# CAN_Module.net
KiCad netlist of a schematic drawn in Altium Designer
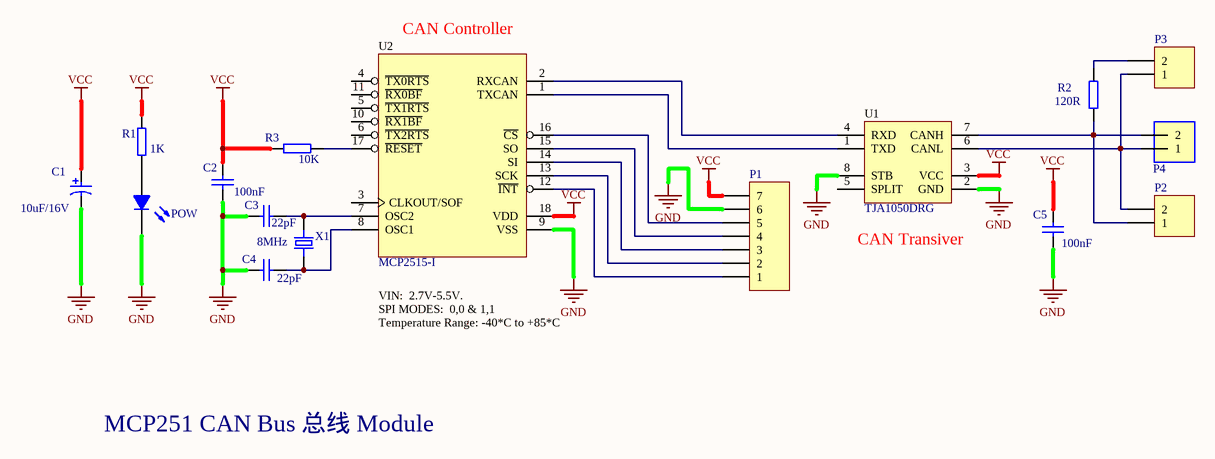
[diagram p0: CAN_Module.SchDoc]

(export (version "E")
  (design (tool "Eeschema 10.0.6"))
  (components
    (comp (ref "C1")
      (value "10uF/16V")
      (footprint "tantalum  A")
      (description "SMD Tantalum Capacitor")
      (libsource (lib "adafruit") (part "Cap_Tantalum"))
    )
    (comp (ref "C2")
      (value "100nF")
      (footprint "C0603")
      (description "Capacitor, X5R, ±10%, 6.3V")
      (fields
        (field (name "PART NUMBER") "C0603-N.C.")
        (field (name "MANUFACTURER") "N.A.")
        (field (name "PUBLISHER") "Nordic Semiconductor")
      )
      (libsource (lib "adafruit") (part "Cap_0603"))
    )
    (comp (ref "C3")
      (value "22pF")
      (footprint "C0603")
      (description "Capacitor, X5R, ±10%, 6.3V")
      (fields
        (field (name "PART NUMBER") "C0603-N.C.")
        (field (name "MANUFACTURER") "N.A.")
        (field (name "PUBLISHER") "Nordic Semiconductor")
      )
      (libsource (lib "adafruit") (part "Cap_0603"))
    )
    (comp (ref "C4")
      (value "22pF")
      (footprint "C0603")
      (description "Capacitor, X5R, ±10%, 6.3V")
      (fields
        (field (name "PART NUMBER") "C0603-N.C.")
        (field (name "MANUFACTURER") "N.A.")
        (field (name "PUBLISHER") "Nordic Semiconductor")
      )
      (libsource (lib "adafruit") (part "Cap_0603"))
    )
    (comp (ref "C5")
      (value "100nF")
      (footprint "C0603")
      (description "Capacitor, X5R, ±10%, 6.3V")
      (fields
        (field (name "PART NUMBER") "C0603-N.C.")
        (field (name "MANUFACTURER") "N.A.")
        (field (name "PUBLISHER") "Nordic Semiconductor")
      )
      (libsource (lib "adafruit") (part "Cap_0603"))
    )
    (comp (ref "P1")
      (value "Header 7")
      (footprint "HDR1X7")
      (description "Header, 7-Pin")
      (fields (field (name "PUBLISHER") "Altium Limited"))
      (libsource (lib "Miscellaneous Connectors") (part "Header 7"))
    )
    (comp (ref "P2")
      (value "Header 2")
      (footprint "HDR1X2")
      (description "Header, 2-Pin")
      (fields (field (name "PUBLISHER") "Altium Limited"))
      (libsource (lib "adafruit") (part "Header 2"))
    )
    (comp (ref "P3")
      (value "Header 2")
      (footprint "HDR1X2")
      (description "Header, 2-Pin")
      (fields (field (name "PUBLISHER") "Altium Limited"))
      (libsource (lib "adafruit") (part "Header 2"))
    )
    (comp (ref "P4")
      (value "Terminal Block 3.5mmPitch: 3,5 mmNumber of pins: 2Created by Rembrandt Electronicswww.rembrandtelectronics.com")
      (footprint "TERMINAL-BLOCK-2-PIN-3.5MM-ROUND-PAD")
      (description "Screw Terminal 3.5mm")
      (libsource (lib "adafruit") (part "TERMINAL-3.50-2P"))
    )
    (comp (ref "POW")
      (value "RED LED")
      (footprint "CHIPLED_0603")
      (description "SMD lamp beads")
      (libsource (lib "adafruit") (part "LEDCHIP-LED0603"))
    )
    (comp (ref "R1")
      (value "1kΩ")
      (footprint "R0603")
      (description "Resistor, ±1%, 0.100W")
      (fields
        (field (name "PART NUMBER") "R0603-N.C.Ω")
        (field (name "MANUFACTURER") "N.A.")
        (field (name "PUBLISHER") "Nordic Semiconductor")
      )
      (libsource (lib "") (part "Res_0603_1"))
    )
    (comp (ref "R2")
      (value "120Ω")
      (footprint "R0603")
      (description "Resistor, ±1%, 0.100W")
      (fields
        (field (name "PART NUMBER") "R0603-N.C.Ω")
        (field (name "MANUFACTURER") "N.A.")
        (field (name "PUBLISHER") "Nordic Semiconductor")
      )
      (libsource (lib "") (part "Res_0603_2"))
    )
    (comp (ref "R3")
      (value "10kΩ")
      (footprint "R0603")
      (description "Resistor, ±1%, 0.100W")
      (fields
        (field (name "PART NUMBER") "R0603-N.C.Ω")
        (field (name "MANUFACTURER") "N.A.")
        (field (name "PUBLISHER") "Nordic Semiconductor")
      )
      (libsource (lib "adafruit") (part "Res_0603"))
    )
    (comp (ref "U1")
      (value "TJA1050DRG")
      (footprint "SOIC-8E")
      (description "CAN Transiver")
      (fields (field (name "MANUFACTURER") "HGC(深圳汉芯)"))
      (libsource (lib "adafruit") (part "TJA1050DRG"))
    )
    (comp (ref "U2")
      (value "MCP2515-I")
      (footprint "SOIC-18_L11.6-W7.5-P1.27-LS10.3-BL")
      (description "CAN Controller")
      (fields (field (name "MANUFACTURER") "Tokmas(托克马斯)"))
      (libsource (lib "adafruit") (part "MCP2515"))
    )
    (comp (ref "X1")
      (value "8MHz")
      (footprint "HC-49US_L11.5-W4.5-P4.88")
      (description "10MHz Â±30ppm Crystal 20pF 60 Ohms HC-49/US")
      (fields (field (name "MP") "ECS-100-20-5PVX") (field (name "MF") "ECS Inc."))
      (libsource (lib "adafruit") (part "CRYSTAL-ECS-100-20-5PVX"))
    )
  )
  (nets
    (net (code "1") (name "GND") (class "Default")
      (node (ref "C1") (pin "2") (pinfunction "2_2") (pintype "passive"))
      (node (ref "C2") (pin "1") (pinfunction "1_1") (pintype "passive"))
      (node (ref "C3") (pin "2") (pinfunction "2_2") (pintype "passive"))
      (node (ref "C4") (pin "2") (pinfunction "2_2") (pintype "passive"))
      (node (ref "C5") (pin "1") (pinfunction "1_1") (pintype "passive"))
      (node (ref "P1") (pin "6") (pinfunction "6_6") (pintype "passive"))
      (node (ref "POW") (pin "C") (pinfunction "K_C") (pintype "passive"))
      (node (ref "U1") (pin "2") (pinfunction "GND_2") (pintype "passive"))
      (node (ref "U1") (pin "8") (pinfunction "STB_8") (pintype "passive"))
      (node (ref "U2") (pin "9") (pinfunction "VSS_9") (pintype "passive"))
    )
    (net (code "2") (name "Net-(P3-Pad2)") (class "Default")
      (node (ref "P3") (pin "2") (pinfunction "2_2") (pintype "passive"))
      (node (ref "R2") (pin "2") (pinfunction "2_2") (pintype "passive"))
    )
    (net (code "3") (name "Net-(POW-PadA)") (class "Default")
      (node (ref "POW") (pin "A") (pinfunction "A_A") (pintype "passive"))
      (node (ref "R1") (pin "2") (pinfunction "2_2") (pintype "passive"))
    )
    (net (code "4") (name "Net-(U1-CANH)") (class "Default")
      (node (ref "P2") (pin "1") (pinfunction "1_1") (pintype "passive"))
      (node (ref "P4") (pin "2") (pinfunction "2_2") (pintype "passive"))
      (node (ref "R2") (pin "1") (pinfunction "1_1") (pintype "passive"))
      (node (ref "U1") (pin "7") (pinfunction "CANH_7") (pintype "passive"))
    )
    (net (code "5") (name "Net-(U1-CANL)") (class "Default")
      (node (ref "P2") (pin "2") (pinfunction "2_2") (pintype "passive"))
      (node (ref "P3") (pin "1") (pinfunction "1_1") (pintype "passive"))
      (node (ref "P4") (pin "1") (pinfunction "1_1") (pintype "passive"))
      (node (ref "U1") (pin "6") (pinfunction "CANL_6") (pintype "passive"))
    )
    (net (code "6") (name "Net-(U1-RXD)") (class "Default")
      (node (ref "U1") (pin "4") (pinfunction "RXD_4") (pintype "passive"))
      (node (ref "U2") (pin "2") (pinfunction "RXCAN_2") (pintype "passive"))
    )
    (net (code "7") (name "Net-(U1-TXD)") (class "Default")
      (node (ref "U1") (pin "1") (pinfunction "TXD_1") (pintype "passive"))
      (node (ref "U2") (pin "1") (pinfunction "TXCAN_1") (pintype "passive"))
    )
    (net (code "8") (name "Net-(U2-OSC1)") (class "Default")
      (node (ref "C4") (pin "1") (pinfunction "1_1") (pintype "passive"))
      (node (ref "U2") (pin "8") (pinfunction "OSC1_8") (pintype "passive"))
      (node (ref "X1") (pin "1") (pinfunction "1_1") (pintype "passive"))
    )
    (net (code "9") (name "Net-(U2-OSC2)") (class "Default")
      (node (ref "C3") (pin "1") (pinfunction "1_1") (pintype "passive"))
      (node (ref "U2") (pin "7") (pinfunction "OSC2_7") (pintype "passive"))
      (node (ref "X1") (pin "2") (pinfunction "2_2") (pintype "passive"))
    )
    (net (code "10") (name "Net-(U2-SCK)") (class "Default")
      (node (ref "P1") (pin "2") (pinfunction "2_2") (pintype "passive"))
      (node (ref "U2") (pin "13") (pinfunction "SCK_13") (pintype "passive"))
    )
    (net (code "11") (name "Net-(U2-SI)") (class "Default")
      (node (ref "P1") (pin "3") (pinfunction "3_3") (pintype "passive"))
      (node (ref "U2") (pin "14") (pinfunction "SI_14") (pintype "passive"))
    )
    (net (code "12") (name "Net-(U2-SO)") (class "Default")
      (node (ref "P1") (pin "4") (pinfunction "4_4") (pintype "passive"))
      (node (ref "U2") (pin "15") (pinfunction "SO_15") (pintype "passive"))
    )
    (net (code "13") (name "Net-(U2-~{CS})") (class "Default")
      (node (ref "P1") (pin "5") (pinfunction "5_5") (pintype "passive"))
      (node (ref "U2") (pin "16") (pinfunction "~{CS}_16") (pintype "passive"))
    )
    (net (code "14") (name "Net-(U2-~{INT})") (class "Default")
      (node (ref "P1") (pin "1") (pinfunction "1_1") (pintype "passive"))
      (node (ref "U2") (pin "12") (pinfunction "~{INT}_12") (pintype "passive"))
    )
    (net (code "15") (name "Net-(U2-~{RESET})") (class "Default")
      (node (ref "R3") (pin "1") (pinfunction "1_1") (pintype "passive"))
      (node (ref "U2") (pin "17") (pinfunction "~{RESET}_17") (pintype "passive"))
    )
    (net (code "16") (name "VCC") (class "Default")
      (node (ref "C1") (pin "1") (pinfunction "1_1") (pintype "passive"))
      (node (ref "C2") (pin "2") (pinfunction "2_2") (pintype "passive"))
      (node (ref "C5") (pin "2") (pinfunction "2_2") (pintype "passive"))
      (node (ref "P1") (pin "7") (pinfunction "7_7") (pintype "passive"))
      (node (ref "R1") (pin "1") (pinfunction "1_1") (pintype "passive"))
      (node (ref "R3") (pin "2") (pinfunction "2_2") (pintype "passive"))
      (node (ref "U1") (pin "3") (pinfunction "VCC_3") (pintype "passive"))
      (node (ref "U2") (pin "18") (pinfunction "VDD_18") (pintype "passive"))
    )
    (net (code "17") (name "unconnected-(U1-SPLIT-Pad5)") (class "Default")
      (node (ref "U1") (pin "5") (pinfunction "SPLIT_5") (pintype "passive"))
    )
    (net (code "18") (name "unconnected-(U2-CLKOUT{slash}SOF-Pad3)") (class "Default")
      (node (ref "U2") (pin "3") (pinfunction "CLKOUT/SOF_3") (pintype "passive"))
    )
    (net (code "19") (name "unconnected-(U2-~{RX0BF}-Pad11)") (class "Default")
      (node (ref "U2") (pin "11") (pinfunction "~{RX0BF}_11") (pintype "passive"))
    )
    (net (code "20") (name "unconnected-(U2-~{RX1BF}-Pad10)") (class "Default")
      (node (ref "U2") (pin "10") (pinfunction "~{RX1BF}_10") (pintype "passive"))
    )
    (net (code "21") (name "unconnected-(U2-~{TX0RTS}-Pad4)") (class "Default")
      (node (ref "U2") (pin "4") (pinfunction "~{TX0RTS}_4") (pintype "passive"))
    )
    (net (code "22") (name "unconnected-(U2-~{TX1RTS}-Pad5)") (class "Default")
      (node (ref "U2") (pin "5") (pinfunction "~{TX1RTS}_5") (pintype "passive"))
    )
    (net (code "23") (name "unconnected-(U2-~{TX2RTS}-Pad6)") (class "Default")
      (node (ref "U2") (pin "6") (pinfunction "~{TX2RTS}_6") (pintype "passive"))
    )
  )
)
